# Power.net
KiCad netlist of a schematic drawn in Altium Designer
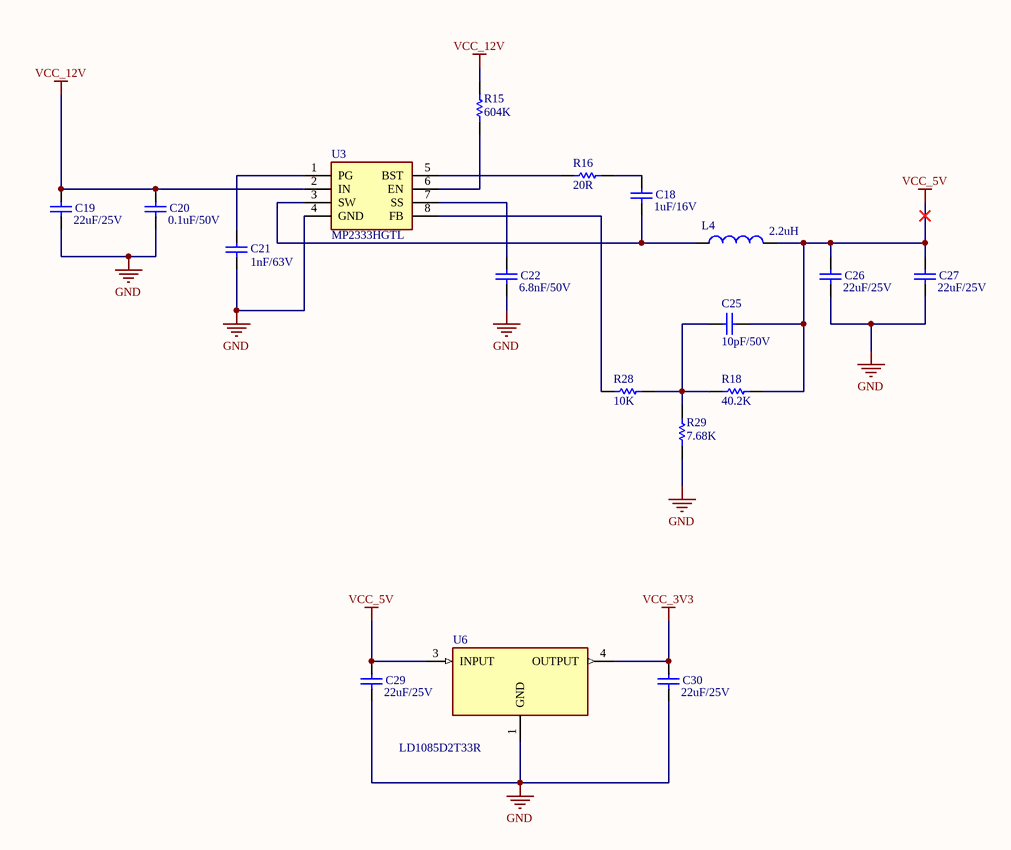
[diagram p0: Power.SchDoc]

(export (version "E")
  (design (tool "Eeschema 10.0.6"))
  (components
    (comp (ref "C18")
      (value "1uF/16V")
      (footprint "0603C")
      (description "Multilayer Ceramic Capacitors MLCC - SMD/SMT 16volts 1uF X7R 10%")
      (fields (field (name "MFR") "KEMET") (field (name "MFR PART NO") "C0603C105K4RAC7411"))
      (libsource (lib "Miscellaneous Devices") (part "Cap"))
    )
    (comp (ref "C19")
      (value "22uF/25V")
      (footprint "1210C")
      (description "Multilayer Ceramic Capacitors MLCC - SMD/SMT 1210 25VDC 22uF 20% X7R AEC-Q200")
      (fields (field (name "MFR") "Taiyo Yuden") (field (name "MFR PART NO") "TMK325B7226MMHP"))
      (libsource (lib "Miscellaneous Devices") (part "Cap"))
    )
    (comp (ref "C20")
      (value "0.1uF/50V")
      (footprint "0603C")
      (description "Multilayer Ceramic Capacitors MLCC - SMD/SMT 50V 0.1uF 0603 X7R 20%")
      (fields (field (name "MFR") "KEMET") (field (name "MFR PART NO") "C0603C104M5RACTU"))
      (libsource (lib "Miscellaneous Devices") (part "Cap"))
    )
    (comp (ref "C21")
      (value "1nF/63V")
      (footprint "0603C")
      (description "Multilayer Ceramic Capacitors MLCC - SMD/SMT 63V 1000pF 0603 X7R 10% AEC-Q200")
      (fields (field (name "MFR") "KEMET") (field (name "MFR PART NO") "80-C0603C102KMREAUTO"))
      (libsource (lib "Miscellaneous Devices") (part "Cap"))
    )
    (comp (ref "C22")
      (value "6.8nF/50V")
      (footprint "0603C")
      (description "Multilayer Ceramic Capacitors MLCC - SMD/SMT 0603 50VDC 6.8nF 5% C0G AEC-Q200")
      (fields (field (name "MFR") "TDK") (field (name "MFR PART NO") "CGA3E2C0G1H682J080AE"))
      (libsource (lib "Miscellaneous Devices") (part "Cap"))
    )
    (comp (ref "C25")
      (value "10pF/50V")
      (footprint "0603C")
      (description "Multilayer Ceramic Capacitors MLCC - SMD/SMT 50V 10pF 0603 C0G 5% AEC-Q200")
      (fields (field (name "MFR") "KEMET") (field (name "MFR PART NO") "C0603C100J5GACAUTO"))
      (libsource (lib "Miscellaneous Devices") (part "Cap"))
    )
    (comp (ref "C26")
      (value "22uF/25V")
      (footprint "1210C")
      (description "Multilayer Ceramic Capacitors MLCC - SMD/SMT 1210 25VDC 22uF 20% X7R AEC-Q200")
      (fields (field (name "MFR") "Taiyo Yuden") (field (name "MFR PART NO") "TMK325B7226MMHP"))
      (libsource (lib "Miscellaneous Devices") (part "Cap"))
    )
    (comp (ref "C27")
      (value "22uF/25V")
      (footprint "1210C")
      (description "Multilayer Ceramic Capacitors MLCC - SMD/SMT 1210 25VDC 22uF 20% X7R AEC-Q200")
      (fields (field (name "MFR") "Taiyo Yuden") (field (name "MFR PART NO") "TMK325B7226MMHP"))
      (libsource (lib "Miscellaneous Devices") (part "Cap"))
    )
    (comp (ref "C29")
      (value "22uF/25V")
      (footprint "1210C")
      (description "Multilayer Ceramic Capacitors MLCC - SMD/SMT 1210 25VDC 22uF 20% X7R AEC-Q200")
      (fields (field (name "MFR") "Taiyo Yuden") (field (name "MFR PART NO") "TMK325B7226MMHP"))
      (libsource (lib "Miscellaneous Devices") (part "Cap"))
    )
    (comp (ref "C30")
      (value "22uF/25V")
      (footprint "1210C")
      (description "Multilayer Ceramic Capacitors MLCC - SMD/SMT 1210 25VDC 22uF 20% X7R AEC-Q200")
      (fields (field (name "MFR") "Taiyo Yuden") (field (name "MFR PART NO") "TMK325B7226MMHP"))
      (libsource (lib "Miscellaneous Devices") (part "Cap"))
    )
    (comp (ref "L4")
      (value "2.2uH")
      (footprint "IHLP1616BZER2R2M5A")
      (description "Fixed Inductors 2.2uH 20% High Temp AEC-Q200")
      (fields (field (name "MFR") "Vishay / Dale") (field (name "MFR PART NO") "IHLP1616BZER2R2M5A"))
      (libsource (lib "de20") (part "INDUCTOR"))
    )
    (comp (ref "R15")
      (value "604K")
      (footprint "0603R")
      (description "Thick Film Resistors - SMD 0603 1% 604Kohm Anti-Sulfur AEC-Q200")
      (fields (field (name "MFR") "Panasonic") (field (name "MFR PART NO") "ERJ-U03F6043V"))
      (libsource (lib "Miscellaneous Devices") (part "Res1"))
    )
    (comp (ref "R16")
      (value "20R")
      (footprint "0603R")
      (description "Thick Film Resistors - SMD 0603 0.25W 1% 20ohm AEC-Q200")
      (fields (field (name "MFR") "Panasonic") (field (name "MFR PART NO") "ERJ-UP3F20R0V"))
      (libsource (lib "Miscellaneous Devices") (part "Res1"))
    )
    (comp (ref "R18")
      (value "40.2K")
      (footprint "0603R")
      (description "Thick Film Resistors - SMD 0603 Anti-Surge Res. 0.1%, 40.2Koh")
      (fields (field (name "MFR") "Panasonic") (field (name "MFR PART NO") "ERJ-PB3B4022V"))
      (libsource (lib "Miscellaneous Devices") (part "Res1"))
    )
    (comp (ref "R28")
      (value "10K")
      (footprint "0603R")
      (description "Thick Film Resistors - SMD 0603 10Kohms 1% Anti-Sulfur AEC-Q200")
      (fields (field (name "MFR") "ROHM Semiconductor") (field (name "MFR PART NO") "SFR03EZPF1002"))
      (libsource (lib "Miscellaneous Devices") (part "Res1"))
    )
    (comp (ref "R29")
      (value "7.68K")
      (footprint "0603R")
      (description "Thick Film Resistors - SMD 0603 Anti-Surge Res. 0.1%, 7.68Koh")
      (fields (field (name "MFR") "Panasonic") (field (name "MFR PART NO") "ERJ-PB3B7681V"))
      (libsource (lib "Miscellaneous Devices") (part "Res1"))
    )
    (comp (ref "U3")
      (value "MP2333HGTL")
      (footprint "MP2333HGTL-P")
      (description "Switching Voltage Regulators High-Efficiency, 3A, 18V, 1200kHz, Synchronous, Step-Down Converter")
      (fields
        (field (name "MFR") "Monolithic Power Systems (MPS)")
        (field (name "MFR PART NO") "MP2333HGTL-P")
      )
      (libsource (lib "*") (part "MP2333HGTL"))
    )
    (comp (ref "U6")
      (value "LD1085D2T33R")
      (footprint "SamacSys:LD1085D2T33R")
      (description "Integrated Circuit")
      (fields
        (field (name "MFR") "STMicroelectronics")
        (field (name "STOCKIEST PART NO") "511-LD1085D2T33-TR")
      )
      (libsource (lib "*") (part "LD1085D2T33R"))
    )
  )
  (nets
    (net (code "1") (name "GND") (class "Default")
      (node (ref "C19") (pin "1") (pinfunction "1_1") (pintype "passive"))
      (node (ref "C20") (pin "1") (pinfunction "1_1") (pintype "passive"))
      (node (ref "C21") (pin "1") (pinfunction "1_1") (pintype "passive"))
      (node (ref "C22") (pin "1") (pinfunction "1_1") (pintype "passive"))
      (node (ref "C26") (pin "1") (pinfunction "1_1") (pintype "passive"))
      (node (ref "C27") (pin "1") (pinfunction "1_1") (pintype "passive"))
      (node (ref "C29") (pin "1") (pinfunction "1_1") (pintype "passive"))
      (node (ref "C30") (pin "1") (pinfunction "1_1") (pintype "passive"))
      (node (ref "R29") (pin "2") (pinfunction "2_2") (pintype "passive"))
      (node (ref "U3") (pin "4") (pinfunction "GND_4") (pintype "passive"))
      (node (ref "U6") (pin "1") (pinfunction "GND_1") (pintype "power_in"))
    )
    (net (code "2") (name "Net-(C18-Pad2)") (class "Default")
      (node (ref "C18") (pin "2") (pinfunction "2_2") (pintype "passive"))
      (node (ref "R16") (pin "2") (pinfunction "2_2") (pintype "passive"))
    )
    (net (code "3") (name "Net-(C25-Pad2)") (class "Default")
      (node (ref "C25") (pin "2") (pinfunction "2_2") (pintype "passive"))
      (node (ref "R18") (pin "1") (pinfunction "1_1") (pintype "passive"))
      (node (ref "R28") (pin "1") (pinfunction "1_1") (pintype "passive"))
      (node (ref "R29") (pin "1") (pinfunction "1_1") (pintype "passive"))
    )
    (net (code "4") (name "Net-(U3-BST)") (class "Default")
      (node (ref "R16") (pin "1") (pinfunction "1_1") (pintype "passive"))
      (node (ref "U3") (pin "5") (pinfunction "BST_5") (pintype "passive"))
    )
    (net (code "5") (name "Net-(U3-EN)") (class "Default")
      (node (ref "R15") (pin "1") (pinfunction "1_1") (pintype "passive"))
      (node (ref "U3") (pin "6") (pinfunction "EN_6") (pintype "passive"))
    )
    (net (code "6") (name "Net-(U3-FB)") (class "Default")
      (node (ref "R28") (pin "2") (pinfunction "2_2") (pintype "passive"))
      (node (ref "U3") (pin "8") (pinfunction "FB_8") (pintype "passive"))
    )
    (net (code "7") (name "Net-(U3-PG)") (class "Default")
      (node (ref "C21") (pin "2") (pinfunction "2_2") (pintype "passive"))
      (node (ref "U3") (pin "1") (pinfunction "PG_1") (pintype "passive"))
    )
    (net (code "8") (name "Net-(U3-SS)") (class "Default")
      (node (ref "C22") (pin "2") (pinfunction "2_2") (pintype "passive"))
      (node (ref "U3") (pin "7") (pinfunction "SS_7") (pintype "passive"))
    )
    (net (code "9") (name "Net-(U3-SW)") (class "Default")
      (node (ref "C18") (pin "1") (pinfunction "1_1") (pintype "passive"))
      (node (ref "L4") (pin "1") (pinfunction "1_1") (pintype "passive"))
      (node (ref "U3") (pin "3") (pinfunction "SW_3") (pintype "passive"))
    )
    (net (code "10") (name "VCC_3V3") (class "Default")
      (node (ref "C30") (pin "2") (pinfunction "2_2") (pintype "passive"))
      (node (ref "U6") (pin "4") (pinfunction "OUTPUT_4") (pintype "output"))
    )
    (net (code "11") (name "VCC_5V") (class "Default")
      (node (ref "C25") (pin "1") (pinfunction "1_1") (pintype "passive"))
      (node (ref "C26") (pin "2") (pinfunction "2_2") (pintype "passive"))
      (node (ref "C27") (pin "2") (pinfunction "2_2") (pintype "passive"))
      (node (ref "C29") (pin "2") (pinfunction "2_2") (pintype "passive"))
      (node (ref "L4") (pin "2") (pinfunction "2_2") (pintype "passive"))
      (node (ref "R18") (pin "2") (pinfunction "2_2") (pintype "passive"))
      (node (ref "U6") (pin "3") (pinfunction "INPUT_3") (pintype "input"))
    )
    (net (code "12") (name "VCC_12V") (class "Default")
      (node (ref "C19") (pin "2") (pinfunction "2_2") (pintype "passive"))
      (node (ref "C20") (pin "2") (pinfunction "2_2") (pintype "passive"))
      (node (ref "R15") (pin "2") (pinfunction "2_2") (pintype "passive"))
      (node (ref "U3") (pin "2") (pinfunction "IN_2") (pintype "passive"))
    )
  )
)
